# Sheet1.net
KiCad netlist of a schematic drawn in Altium Designer
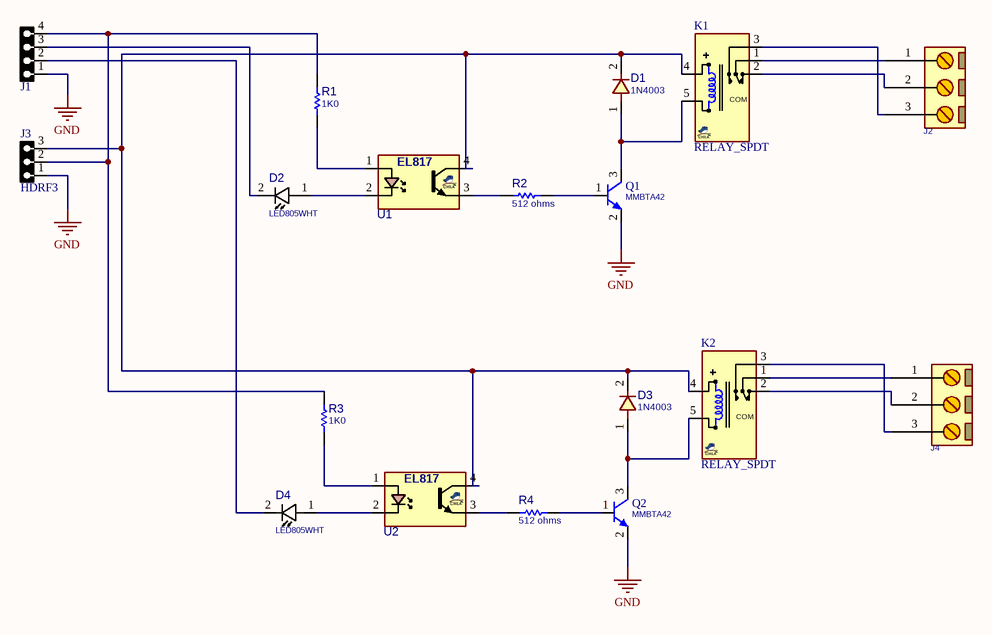
[diagram p0: Sheet1.SchDoc]

(export (version "E")
  (design (tool "Eeschema 10.0.6"))
  (components
    (comp (ref "D1")
      (value "1N4003")
      (footprint "D_SMA")
      (description "DIODE, GENERAL PURPOSE, 200V/1A")
      (fields (field (name "MANF") "MANF"))
      (libsource (lib "diode") (part "DIODE_SMD_1N4003"))
    )
    (comp (ref "D2")
      (value "LED805WHT")
      (footprint "LED0805WHT")
      (description "LED, SMD, 0805, WHITE")
      (fields (field (name "MANF") "MANF") (field (name "MANF_P#") "MANF_PART#"))
      (libsource (lib "led(diode)") (part "LED_SMD_0805_WHT"))
    )
    (comp (ref "D3")
      (value "1N4003")
      (footprint "D_SMA")
      (description "DIODE, GENERAL PURPOSE, 200V/1A")
      (fields (field (name "MANF") "MANF"))
      (libsource (lib "diode") (part "DIODE_SMD_1N4003"))
    )
    (comp (ref "D4")
      (value "LED805WHT")
      (footprint "LED0805WHT")
      (description "LED, SMD, 0805, WHITE")
      (fields (field (name "MANF") "MANF") (field (name "MANF_P#") "MANF_PART#"))
      (libsource (lib "led(diode)") (part "LED_SMD_0805_WHT"))
    )
    (comp (ref "J1")
      (value "HDRF4")
      (footprint "HDRRS_F_1X4")
      (description "CONN, HEADER, Female, pitch: 2.54mm, 4POS")
      (libsource (lib "conn_header_2.54mm_ra_smd") (part "HDRRS_F_1X4"))
    )
    (comp (ref "J2")
      (value "CONN_TB3")
      (footprint "TBB_3")
      (description "CONN, TERMINAL BLOCK, 5.08mm pitch")
      (libsource (lib "conn_terminalB") (part "CONN_TB3"))
    )
    (comp (ref "J3")
      (value "HDRF3")
      (footprint "HDRRS_F_1X3")
      (description "CONN, HEADER, Female, pitch: 2.54mm, 3POS")
      (libsource (lib "conn_header_2.54mm_ra_smd") (part "HDRRS_F_1X3"))
    )
    (comp (ref "J4")
      (value "CONN_TB3")
      (footprint "TBB_3")
      (description "CONN, TERMINAL BLOCK, 5.08mm pitch")
      (libsource (lib "conn_terminalB") (part "CONN_TB3"))
    )
    (comp (ref "K1")
      (value "RELAY_SPDT")
      (footprint "REL_SPDT_5_1611")
      (description "Relay, SPDT, 5P, 15.5X11mm, TRB 125VAC/1A")
      (fields (field (name "MANF") "TTI") (field (name "MANF_P#") "TRBS-6VDC-SA-CL"))
      (libsource (lib "relay") (part "RELAY_SPDT_5_1611_TRBS"))
    )
    (comp (ref "K2")
      (value "RELAY_SPDT")
      (footprint "REL_SPDT_5_1611")
      (description "Relay, SPDT, 5P, 15.5X11mm, TRB 125VAC/1A")
      (fields (field (name "MANF") "TTI") (field (name "MANF_P#") "TRBS-6VDC-SA-CL"))
      (libsource (lib "relay") (part "RELAY_SPDT_5_1611_TRBS"))
    )
    (comp (ref "Q1")
      (value "MMBTA42")
      (footprint "SOT23_3")
      (description "BJT, NPN, 300v, 0.5A, SMD, SOT23")
      (fields (field (name "MANF") "ON/FAIRCHILD"))
      (libsource (lib "transistor_bjt") (part "NPN_MMBTA42_SOT23"))
    )
    (comp (ref "Q2")
      (value "MMBTA42")
      (footprint "SOT23_3")
      (description "BJT, NPN, 300v, 0.5A, SMD, SOT23")
      (fields (field (name "MANF") "ON/FAIRCHILD"))
      (libsource (lib "transistor_bjt") (part "NPN_MMBTA42_SOT23"))
    )
    (comp (ref "R1")
      (value "1K0")
      (footprint "R0805")
      (description "RESISTOR, SMD")
      (libsource (lib "passive_smd") (part "RES_SMD_0805"))
    )
    (comp (ref "R2")
      (value "512 ohms")
      (footprint "R0805")
      (description "RESISTOR, SMD")
      (libsource (lib "passive_smd") (part "RES_SMD_0805"))
    )
    (comp (ref "R3")
      (value "1K0")
      (footprint "R0805")
      (description "RESISTOR, SMD")
      (libsource (lib "passive_smd") (part "RES_SMD_0805"))
    )
    (comp (ref "R4")
      (value "512 ohms")
      (footprint "R0805")
      (description "RESISTOR, SMD")
      (libsource (lib "passive_smd") (part "RES_SMD_0805"))
    )
    (comp (ref "U1")
      (value "EL817")
      (footprint "DIP_4SMD")
      (description "OPTOCOUPLER, TRANSISTOR, 4PIN")
      (libsource (lib "optocoupler") (part "OPTC_TR4P_EL817_SMD"))
    )
    (comp (ref "U2")
      (value "EL817")
      (footprint "DIP_4SMD")
      (description "OPTOCOUPLER, TRANSISTOR, 4PIN")
      (libsource (lib "optocoupler") (part "OPTC_TR4P_EL817_SMD"))
    )
  )
  (nets
    (net (code "1") (name "GND") (class "Default")
      (node (ref "J1") (pin "1") (pinfunction "1_1") (pintype "passive"))
      (node (ref "J3") (pin "1") (pinfunction "1_1") (pintype "passive"))
      (node (ref "Q1") (pin "2") (pinfunction "E_2") (pintype "passive"))
      (node (ref "Q2") (pin "2") (pinfunction "E_2") (pintype "passive"))
    )
    (net (code "2") (name "Net-(D2-ANODE)") (class "Default")
      (node (ref "D2") (pin "1") (pinfunction "ANODE_1") (pintype "passive"))
      (node (ref "U1") (pin "2") (pinfunction "K_2") (pintype "passive"))
    )
    (net (code "3") (name "Net-(D2-CATHODE)") (class "Default")
      (node (ref "D2") (pin "2") (pinfunction "CATHODE_2") (pintype "passive"))
      (node (ref "J1") (pin "3") (pinfunction "3_3") (pintype "passive"))
    )
    (net (code "4") (name "Net-(D4-ANODE)") (class "Default")
      (node (ref "D4") (pin "1") (pinfunction "ANODE_1") (pintype "passive"))
      (node (ref "U2") (pin "2") (pinfunction "K_2") (pintype "passive"))
    )
    (net (code "5") (name "Net-(D4-CATHODE)") (class "Default")
      (node (ref "D4") (pin "2") (pinfunction "CATHODE_2") (pintype "passive"))
      (node (ref "J1") (pin "2") (pinfunction "2_2") (pintype "passive"))
    )
    (net (code "6") (name "Net-(J1-Pad4)") (class "Default")
      (node (ref "J1") (pin "4") (pinfunction "4_4") (pintype "passive"))
      (node (ref "J3") (pin "2") (pinfunction "2_2") (pintype "passive"))
      (node (ref "R1") (pin "2") (pinfunction "2_2") (pintype "passive"))
      (node (ref "R3") (pin "2") (pinfunction "2_2") (pintype "passive"))
    )
    (net (code "7") (name "Net-(K1-COM)") (class "Default")
      (node (ref "J2") (pin "1") (pinfunction "1_1") (pintype "passive"))
      (node (ref "K1") (pin "1") (pinfunction "COM_1") (pintype "passive"))
    )
    (net (code "8") (name "Net-(K1-NC)") (class "Default")
      (node (ref "J2") (pin "2") (pinfunction "2_2") (pintype "passive"))
      (node (ref "K1") (pin "2") (pinfunction "NC_2") (pintype "passive"))
    )
    (net (code "9") (name "Net-(K1-NO)") (class "Default")
      (node (ref "J2") (pin "3") (pinfunction "3_3") (pintype "passive"))
      (node (ref "K1") (pin "3") (pinfunction "NO_3") (pintype "passive"))
    )
    (net (code "10") (name "Net-(K1-T1)") (class "Default")
      (node (ref "D1") (pin "2") (pinfunction "2_2") (pintype "passive"))
      (node (ref "D3") (pin "2") (pinfunction "2_2") (pintype "passive"))
      (node (ref "J3") (pin "3") (pinfunction "3_3") (pintype "passive"))
      (node (ref "K1") (pin "4") (pinfunction "T1_4") (pintype "passive"))
      (node (ref "K2") (pin "4") (pinfunction "T1_4") (pintype "passive"))
      (node (ref "U1") (pin "4") (pinfunction "C_4") (pintype "passive"))
      (node (ref "U2") (pin "4") (pinfunction "C_4") (pintype "passive"))
    )
    (net (code "11") (name "Net-(K1-T2)") (class "Default")
      (node (ref "D1") (pin "1") (pinfunction "1_1") (pintype "passive"))
      (node (ref "K1") (pin "5") (pinfunction "T2_5") (pintype "passive"))
      (node (ref "Q1") (pin "3") (pinfunction "C_3") (pintype "passive"))
    )
    (net (code "12") (name "Net-(K2-COM)") (class "Default")
      (node (ref "J4") (pin "1") (pinfunction "1_1") (pintype "passive"))
      (node (ref "K2") (pin "1") (pinfunction "COM_1") (pintype "passive"))
    )
    (net (code "13") (name "Net-(K2-NC)") (class "Default")
      (node (ref "J4") (pin "2") (pinfunction "2_2") (pintype "passive"))
      (node (ref "K2") (pin "2") (pinfunction "NC_2") (pintype "passive"))
    )
    (net (code "14") (name "Net-(K2-NO)") (class "Default")
      (node (ref "J4") (pin "3") (pinfunction "3_3") (pintype "passive"))
      (node (ref "K2") (pin "3") (pinfunction "NO_3") (pintype "passive"))
    )
    (net (code "15") (name "Net-(K2-T2)") (class "Default")
      (node (ref "D3") (pin "1") (pinfunction "1_1") (pintype "passive"))
      (node (ref "K2") (pin "5") (pinfunction "T2_5") (pintype "passive"))
      (node (ref "Q2") (pin "3") (pinfunction "C_3") (pintype "passive"))
    )
    (net (code "16") (name "Net-(Q1-B)") (class "Default")
      (node (ref "Q1") (pin "1") (pinfunction "B_1") (pintype "passive"))
      (node (ref "R2") (pin "2") (pinfunction "2_2") (pintype "passive"))
    )
    (net (code "17") (name "Net-(Q2-B)") (class "Default")
      (node (ref "Q2") (pin "1") (pinfunction "B_1") (pintype "passive"))
      (node (ref "R4") (pin "2") (pinfunction "2_2") (pintype "passive"))
    )
    (net (code "18") (name "Net-(U1-A)") (class "Default")
      (node (ref "R1") (pin "1") (pinfunction "1_1") (pintype "passive"))
      (node (ref "U1") (pin "1") (pinfunction "A_1") (pintype "passive"))
    )
    (net (code "19") (name "Net-(U1-E)") (class "Default")
      (node (ref "R2") (pin "1") (pinfunction "1_1") (pintype "passive"))
      (node (ref "U1") (pin "3") (pinfunction "E_3") (pintype "passive"))
    )
    (net (code "20") (name "Net-(U2-A)") (class "Default")
      (node (ref "R3") (pin "1") (pinfunction "1_1") (pintype "passive"))
      (node (ref "U2") (pin "1") (pinfunction "A_1") (pintype "passive"))
    )
    (net (code "21") (name "Net-(U2-E)") (class "Default")
      (node (ref "R4") (pin "1") (pinfunction "1_1") (pintype "passive"))
      (node (ref "U2") (pin "3") (pinfunction "E_3") (pintype "passive"))
    )
  )
)
